# mcu.net
KiCad netlist of a schematic drawn in Altium Designer
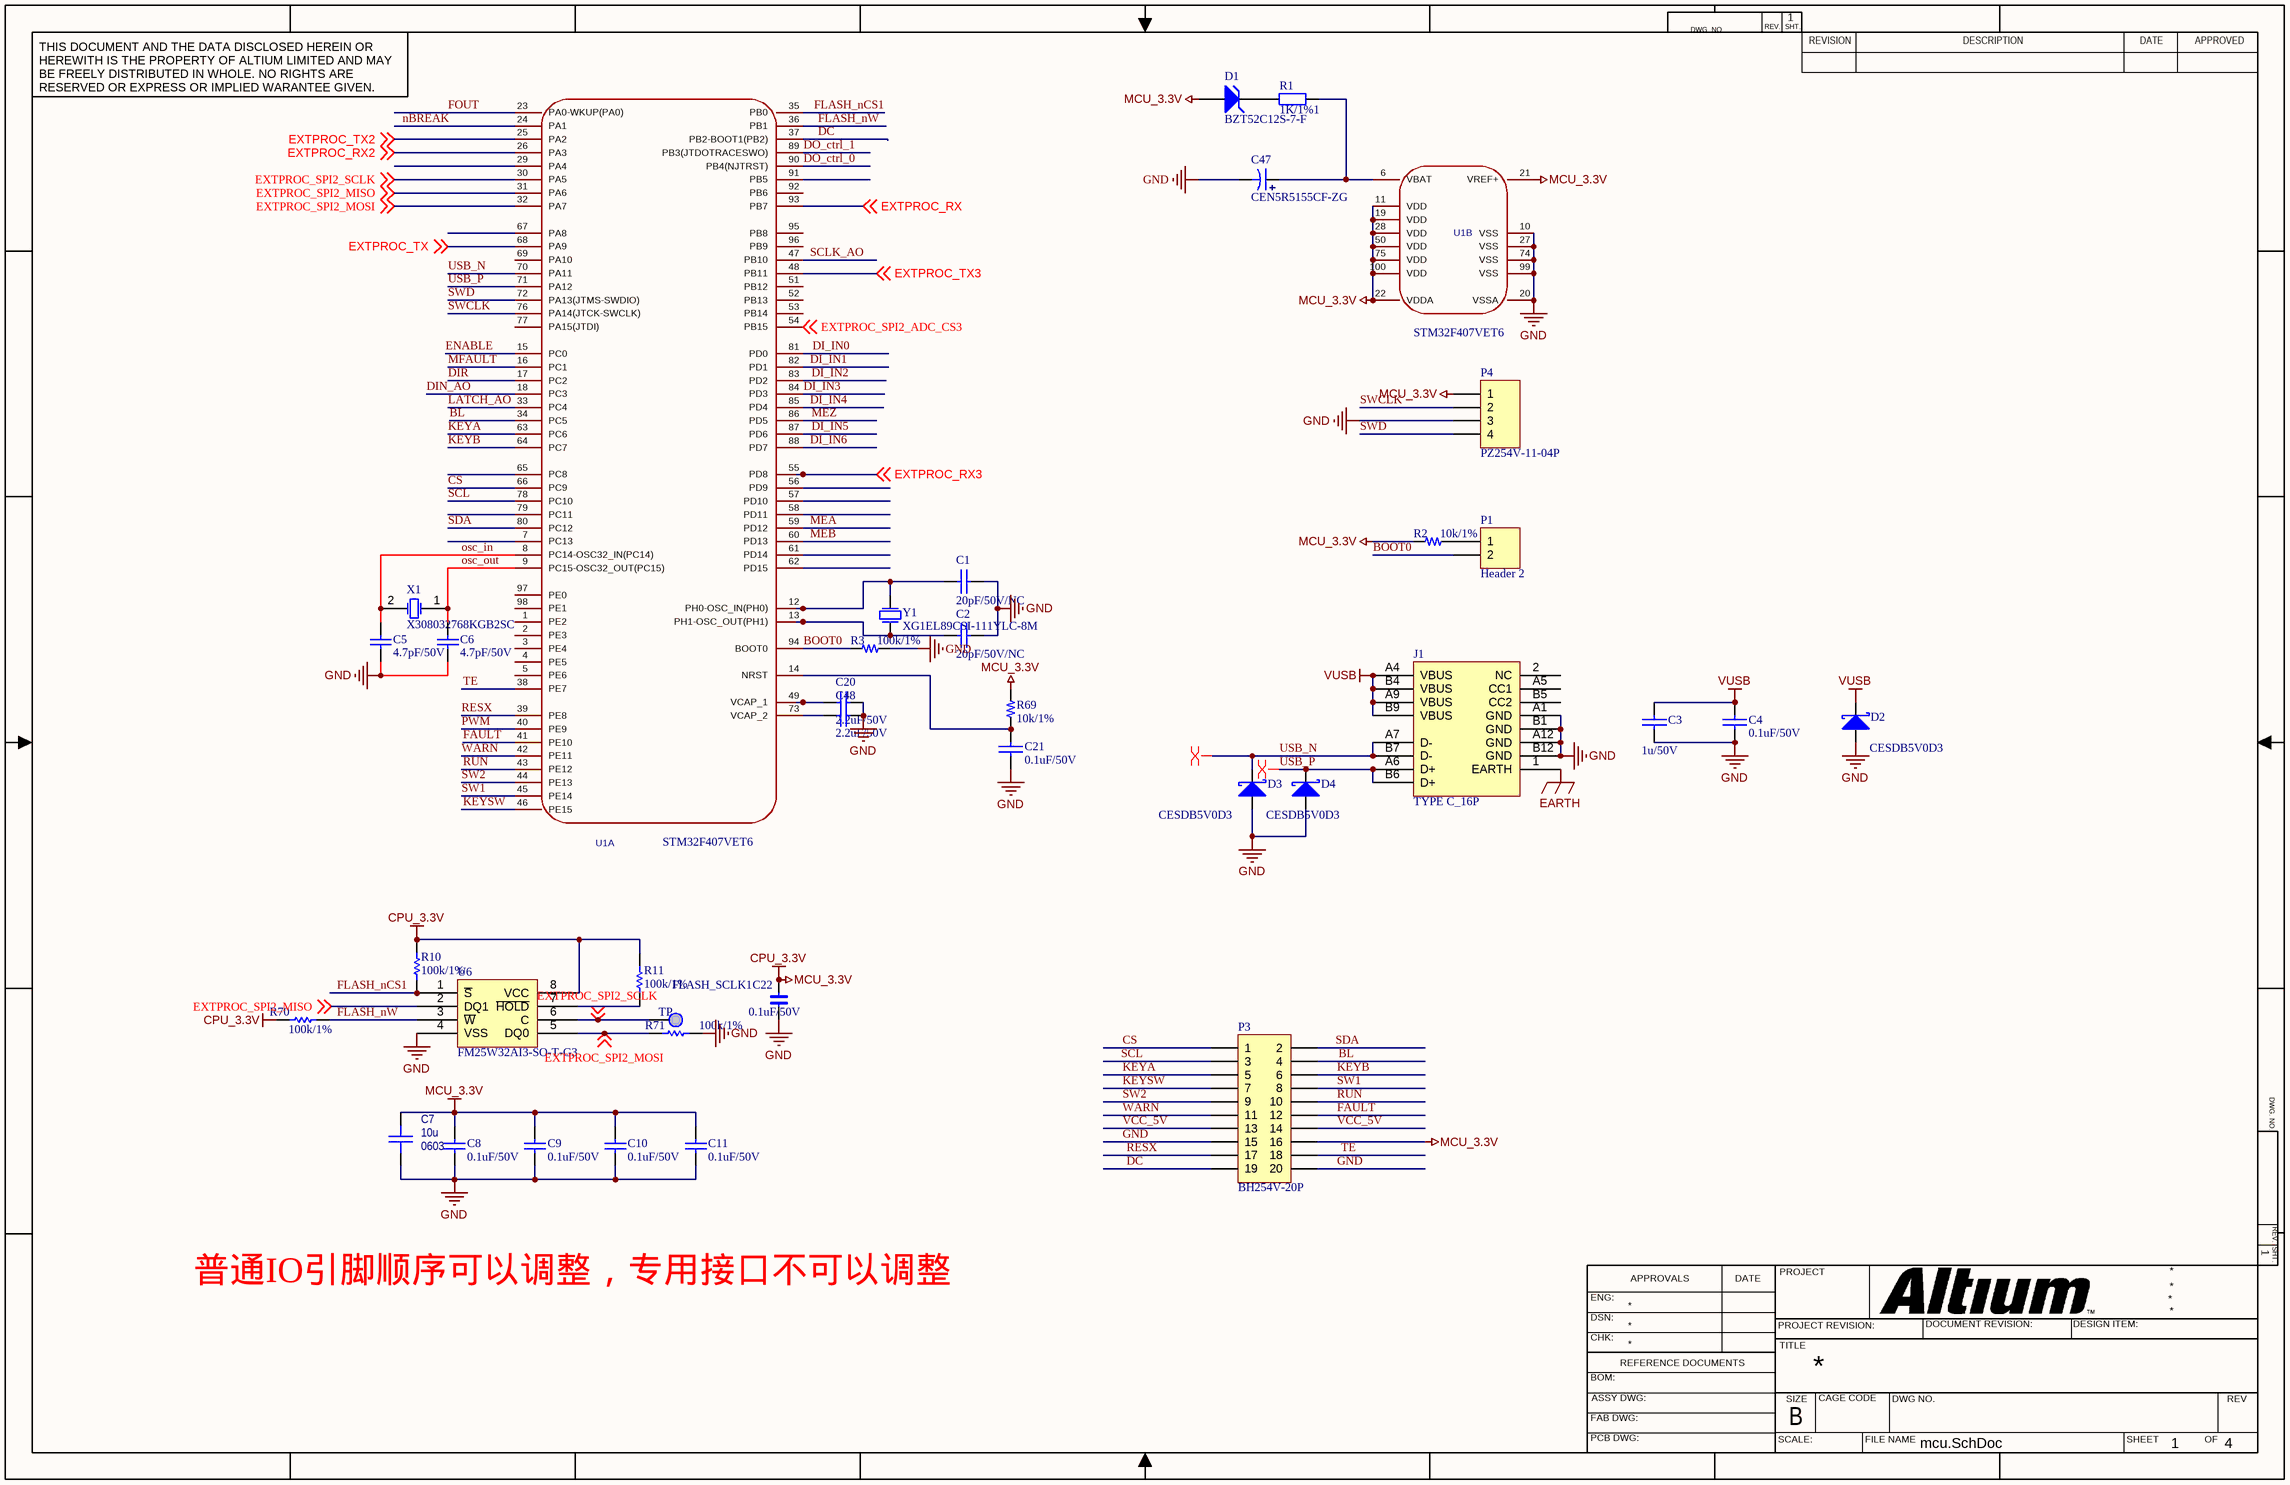
[diagram p0: mcu.SchDoc]

(export (version "E")
  (design (tool "Eeschema 10.0.6"))
  (components
    (comp (ref "C1")
      (value "20pF/50V/NC")
      (footprint "0603C")
      (fields (field (name "Comment") "20pF/25V/NC"))
      (libsource (lib "SM") (part "CAP"))
    )
    (comp (ref "C2")
      (value "20pF/50V/NC")
      (footprint "0603C")
      (fields (field (name "Comment") "20pF/25V/NC"))
      (libsource (lib "SM") (part "CAP"))
    )
    (comp (ref "C3") (value "1u/50V") (footprint "0603C") (libsource (lib "SM") (part "CAP")))
    (comp (ref "C4") (value "0.1uF/50V") (footprint "0603C") (libsource (lib "SM") (part "CAP")))
    (comp (ref "C5")
      (value "4.7pF/50V")
      (footprint "0603C")
      (description "Capacitor")
      (libsource (lib "Miscellaneous Devices") (part "Cap"))
    )
    (comp (ref "C6")
      (value "4.7pF/50V")
      (footprint "0603C")
      (description "Capacitor")
      (libsource (lib "Miscellaneous Devices") (part "Cap"))
    )
    (comp (ref "C7")
      (value "10u")
      (footprint "0603c")
      (description "Capacitor, MLCC")
      (fields (field (name "PACKAGE") "0603") (field (name "Comment") "10uF/16V"))
      (libsource (lib "Karl") (part "Capacitor_0603"))
    )
    (comp (ref "C8")
      (value "0.1uF/50V")
      (footprint "0603C")
      (description "Capacitor")
      (libsource (lib "Miscellaneous Devices") (part "Cap"))
    )
    (comp (ref "C9")
      (value "0.1uF/50V")
      (footprint "0603C")
      (description "Capacitor")
      (libsource (lib "Miscellaneous Devices") (part "Cap"))
    )
    (comp (ref "C10")
      (value "0.1uF/50V")
      (footprint "0603C")
      (description "Capacitor")
      (libsource (lib "Miscellaneous Devices") (part "Cap"))
    )
    (comp (ref "C11")
      (value "0.1uF/50V")
      (footprint "0603C")
      (description "Capacitor")
      (libsource (lib "Miscellaneous Devices") (part "Cap"))
    )
    (comp (ref "C20")
      (value "2.2uF/50V")
      (footprint "0603C")
      (description "Capacitor")
      (libsource (lib "Miscellaneous Devices") (part "Cap"))
    )
    (comp (ref "C21") (value "0.1uF/50V") (footprint "0603C") (libsource (lib "SM") (part "CAP")))
    (comp (ref "C22")
      (value "0.1uF/50V")
      (footprint "0603C")
      (description "C")
      (libsource (lib "Schlib_20110825") (part "C"))
    )
    (comp (ref "C47")
      (value "CEN5R5155CF-ZG")
      (footprint "DTU_V1.0:CAP-TH_BD21.0-P5.00-D0.8_CENXXX-CF")
      (description "电解电容")
      (libsource (lib "XiaoyI") (part "CAP2"))
    )
    (comp (ref "C48")
      (value "2.2uF/50V")
      (footprint "0603C")
      (description "Capacitor")
      (libsource (lib "Miscellaneous Devices") (part "Cap"))
    )
    (comp (ref "D1")
      (value "BZT52C12S-7-F")
      (footprint "DIOD-SOD323-2_V")
      (libsource (lib "Bogen") (part "BZT52C12S-7-F"))
    )
    (comp (ref "D2") (value "CESDB5V0D3") (footprint "SOD323") (libsource (lib "*") (part "DIODE S")))
    (comp (ref "D3") (value "CESDB5V0D3") (footprint "SOD323") (libsource (lib "*") (part "DIODE S")))
    (comp (ref "D4") (value "CESDB5V0D3") (footprint "SOD323") (libsource (lib "*") (part "DIODE S")))
    (comp (ref "FLASH_SCLK1") (value "TP") (footprint "tpd") (libsource (lib "Schlib1") (part "TP")))
    (comp (ref "J1")
      (value "TYPE C_16P")
      (footprint "TYPEC_16P")
      (libsource (lib "Schlib_20110825") (part "TYPE C_16P"))
    )
    (comp (ref "P1")
      (value "Header 2")
      (footprint "HDR1X2")
      (libsource (lib "Miscellaneous Connectors") (part "Header 2"))
    )
    (comp (ref "P3")
      (value "BH254V-20P")
      (footprint "IDC-TH_20P-L33.0-W13.8-H-M-R2-C10-P2.54-S2.54-TR")
      (description "Header, 10-Pin, Dual row")
      (libsource (lib "Miscellaneous Connectors") (part "Header 10X2"))
    )
    (comp (ref "P4")
      (value "PZ254V-11-04P")
      (footprint "HDR1X4")
      (libsource (lib "Miscellaneous Connectors") (part "Header 4"))
    )
    (comp (ref "R1") (value "1K/1%1") (footprint "0603R") (libsource (lib "MQlibrary") (part "Res0805M")))
    (comp (ref "R2") (value "10k/1%") (footprint "0603R") (libsource (lib "JRJ_1") (part "R")))
    (comp (ref "R3") (value "100k/1%") (footprint "0603R") (libsource (lib "JRJ_1") (part "R")))
    (comp (ref "R10")
      (value "100k/1%")
      (footprint "0603R")
      (description "Resistor")
      (libsource (lib "Miscellaneous Devices") (part "Res1"))
    )
    (comp (ref "R11")
      (value "100k/1%")
      (footprint "0603R")
      (description "Resistor")
      (libsource (lib "Miscellaneous Devices") (part "Res1"))
    )
    (comp (ref "R69") (value "10k/1%") (footprint "0603R") (libsource (lib "JRJ_1") (part "R")))
    (comp (ref "R70")
      (value "100k/1%")
      (footprint "0603R")
      (description "Resistor")
      (libsource (lib "Miscellaneous Devices") (part "Res1"))
    )
    (comp (ref "R71")
      (value "100k/1%")
      (footprint "0603R")
      (description "Resistor")
      (libsource (lib "Miscellaneous Devices") (part "Res1"))
    )
    (comp (ref "U1")
      (value "STM32F407VET6")
      (footprint "TQFP-100")
      (libsource (lib "altium-import") (part "root_0_STM32F407VET6_"))
    )
    (comp (ref "U6")
      (value "FM25W32AI3-SO-T-G3")
      (footprint "SOIC127P790X216-8N")
      (libsource (lib "Schlib1") (part "M25P16-VMN6TPBA"))
    )
    (comp (ref "X1")
      (value "X308032768KGB2SC")
      (footprint "A")
      (description "Crystal Oscillator")
      (libsource (lib "Miscellaneous Devices") (part "XTAL"))
    )
    (comp (ref "Y1")
      (value "XG1EL89CSI-111YLC-8M")
      (footprint "CRAY_5032")
      (libsource (lib "") (part "XTAL_1"))
    )
  )
  (nets
    (net (code "1") (name "/BL") (class "Default")
      (node (ref "P3") (pin "4") (pinfunction "4_4") (pintype "passive"))
      (node (ref "U1") (pin "34") (pinfunction "PC5_34") (pintype "passive"))
    )
    (net (code "2") (name "/BOOT0") (class "Default")
      (node (ref "P1") (pin "2") (pinfunction "2_2") (pintype "passive"))
      (node (ref "R3") (pin "1") (pintype "passive"))
      (node (ref "U1") (pin "94") (pinfunction "BOOT0_94") (pintype "passive"))
    )
    (net (code "3") (name "/CS") (class "Default")
      (node (ref "P3") (pin "1") (pinfunction "1_1") (pintype "passive"))
      (node (ref "U1") (pin "66") (pinfunction "PC9_66") (pintype "passive"))
    )
    (net (code "4") (name "/DC") (class "Default")
      (node (ref "P3") (pin "19") (pinfunction "19_19") (pintype "passive"))
      (node (ref "U1") (pin "37") (pinfunction "PB2-BOOT1(PB2)_37") (pintype "passive"))
    )
    (net (code "5") (name "/DIN_AO") (class "Default")
      (node (ref "U1") (pin "18") (pinfunction "PC3_18") (pintype "passive"))
    )
    (net (code "6") (name "/DIR") (class "Default")
      (node (ref "U1") (pin "17") (pinfunction "PC2_17") (pintype "passive"))
    )
    (net (code "7") (name "/DI_IN0") (class "Default")
      (node (ref "U1") (pin "81") (pinfunction "PD0_81") (pintype "passive"))
    )
    (net (code "8") (name "/DI_IN1") (class "Default")
      (node (ref "U1") (pin "82") (pinfunction "PD1_82") (pintype "passive"))
    )
    (net (code "9") (name "/DI_IN2") (class "Default")
      (node (ref "U1") (pin "83") (pinfunction "PD2_83") (pintype "passive"))
    )
    (net (code "10") (name "/DI_IN3") (class "Default")
      (node (ref "U1") (pin "84") (pinfunction "PD3_84") (pintype "passive"))
    )
    (net (code "11") (name "/DI_IN4") (class "Default")
      (node (ref "U1") (pin "85") (pinfunction "PD4_85") (pintype "passive"))
    )
    (net (code "12") (name "/DI_IN5") (class "Default")
      (node (ref "U1") (pin "87") (pinfunction "PD6_87") (pintype "passive"))
    )
    (net (code "13") (name "/DI_IN6") (class "Default")
      (node (ref "U1") (pin "88") (pinfunction "PD7_88") (pintype "passive"))
    )
    (net (code "14") (name "/DO_ctrl_0") (class "Default")
      (node (ref "U1") (pin "90") (pinfunction "PB4(NJTRST)_90") (pintype "passive"))
    )
    (net (code "15") (name "/DO_ctrl_1") (class "Default")
      (node (ref "U1") (pin "89") (pinfunction "PB3(JTDOTRACESWO)_89") (pintype "passive"))
    )
    (net (code "16") (name "/ENABLE") (class "Default")
      (node (ref "U1") (pin "15") (pinfunction "PC0_15") (pintype "passive"))
    )
    (net (code "17") (name "/FAULT") (class "Default")
      (node (ref "P3") (pin "12") (pinfunction "12_12") (pintype "passive"))
      (node (ref "U1") (pin "41") (pinfunction "PE10_41") (pintype "passive"))
    )
    (net (code "18") (name "/FLASH_nCS1") (class "Default")
      (node (ref "R10") (pin "2") (pinfunction "2_2") (pintype "passive"))
      (node (ref "U1") (pin "35") (pinfunction "PB0_35") (pintype "passive"))
      (node (ref "U6") (pin "1") (pinfunction "~{S}_1") (pintype "passive"))
    )
    (net (code "19") (name "/FLASH_nW") (class "Default")
      (node (ref "R70") (pin "2") (pinfunction "2_2") (pintype "passive"))
      (node (ref "U1") (pin "36") (pinfunction "PB1_36") (pintype "passive"))
      (node (ref "U6") (pin "3") (pinfunction "~{W}_3") (pintype "passive"))
    )
    (net (code "20") (name "/FOUT") (class "Default")
      (node (ref "U1") (pin "23") (pinfunction "PA0-WKUP(PA0)_23") (pintype "passive"))
    )
    (net (code "21") (name "/KEYA") (class "Default")
      (node (ref "P3") (pin "5") (pinfunction "5_5") (pintype "passive"))
      (node (ref "U1") (pin "63") (pinfunction "PC6_63") (pintype "passive"))
    )
    (net (code "22") (name "/KEYB") (class "Default")
      (node (ref "P3") (pin "6") (pinfunction "6_6") (pintype "passive"))
      (node (ref "U1") (pin "64") (pinfunction "PC7_64") (pintype "passive"))
    )
    (net (code "23") (name "/KEYSW") (class "Default")
      (node (ref "P3") (pin "7") (pinfunction "7_7") (pintype "passive"))
      (node (ref "U1") (pin "46") (pinfunction "PE15_46") (pintype "passive"))
    )
    (net (code "24") (name "/LATCH_AO") (class "Default")
      (node (ref "U1") (pin "33") (pinfunction "PC4_33") (pintype "passive"))
    )
    (net (code "25") (name "/MEA") (class "Default")
      (node (ref "U1") (pin "59") (pinfunction "PD12_59") (pintype "passive"))
    )
    (net (code "26") (name "/MEB") (class "Default")
      (node (ref "U1") (pin "60") (pinfunction "PD13_60") (pintype "passive"))
    )
    (net (code "27") (name "/MEZ") (class "Default")
      (node (ref "U1") (pin "86") (pinfunction "PD5_86") (pintype "passive"))
    )
    (net (code "28") (name "/MFAULT") (class "Default")
      (node (ref "U1") (pin "16") (pinfunction "PC1_16") (pintype "passive"))
    )
    (net (code "29") (name "/PWM") (class "Default")
      (node (ref "U1") (pin "40") (pinfunction "PE9_40") (pintype "passive"))
    )
    (net (code "30") (name "/RESX") (class "Default")
      (node (ref "P3") (pin "17") (pinfunction "17_17") (pintype "passive"))
      (node (ref "U1") (pin "39") (pinfunction "PE8_39") (pintype "passive"))
    )
    (net (code "31") (name "/RUN") (class "Default")
      (node (ref "P3") (pin "10") (pinfunction "10_10") (pintype "passive"))
      (node (ref "U1") (pin "43") (pinfunction "PE12_43") (pintype "passive"))
    )
    (net (code "32") (name "/SCL") (class "Default")
      (node (ref "P3") (pin "3") (pinfunction "3_3") (pintype "passive"))
      (node (ref "U1") (pin "78") (pinfunction "PC10_78") (pintype "passive"))
    )
    (net (code "33") (name "/SCLK_AO") (class "Default")
      (node (ref "U1") (pin "47") (pinfunction "PB10_47") (pintype "passive"))
    )
    (net (code "34") (name "/SDA") (class "Default")
      (node (ref "P3") (pin "2") (pinfunction "2_2") (pintype "passive"))
      (node (ref "U1") (pin "80") (pinfunction "PC12_80") (pintype "passive"))
    )
    (net (code "35") (name "/SW1") (class "Default")
      (node (ref "P3") (pin "8") (pinfunction "8_8") (pintype "passive"))
      (node (ref "U1") (pin "45") (pinfunction "PE14_45") (pintype "passive"))
    )
    (net (code "36") (name "/SW2") (class "Default")
      (node (ref "P3") (pin "9") (pinfunction "9_9") (pintype "passive"))
      (node (ref "U1") (pin "44") (pinfunction "PE13_44") (pintype "passive"))
    )
    (net (code "37") (name "/SWCLK") (class "Default")
      (node (ref "P4") (pin "2") (pinfunction "2_2") (pintype "passive"))
      (node (ref "U1") (pin "76") (pinfunction "PA14(JTCK-SWCLK)_76") (pintype "passive"))
    )
    (net (code "38") (name "/SWD") (class "Default")
      (node (ref "P4") (pin "4") (pinfunction "4_4") (pintype "passive"))
      (node (ref "U1") (pin "72") (pinfunction "PA13(JTMS-SWDIO)_72") (pintype "passive"))
    )
    (net (code "39") (name "/TE") (class "Default")
      (node (ref "P3") (pin "18") (pinfunction "18_18") (pintype "passive"))
      (node (ref "U1") (pin "38") (pinfunction "PE7_38") (pintype "passive"))
    )
    (net (code "40") (name "/USB_N") (class "Default")
      (node (ref "D3") (pin "2") (pinfunction "K_2") (pintype "passive"))
      (node (ref "J1") (pin "A7") (pinfunction "D-_A7") (pintype "passive"))
      (node (ref "J1") (pin "B7") (pinfunction "D-_B7") (pintype "passive"))
      (node (ref "U1") (pin "70") (pinfunction "PA11_70") (pintype "passive"))
    )
    (net (code "41") (name "/USB_P") (class "Default")
      (node (ref "D4") (pin "2") (pinfunction "K_2") (pintype "passive"))
      (node (ref "J1") (pin "A6") (pinfunction "D+_A6") (pintype "passive"))
      (node (ref "J1") (pin "B6") (pinfunction "D+_B6") (pintype "passive"))
      (node (ref "U1") (pin "71") (pinfunction "PA12_71") (pintype "passive"))
    )
    (net (code "42") (name "/VCC_5V") (class "Default")
      (node (ref "P3") (pin "13") (pinfunction "13_13") (pintype "passive"))
      (node (ref "P3") (pin "14") (pinfunction "14_14") (pintype "passive"))
    )
    (net (code "43") (name "/WARN") (class "Default")
      (node (ref "P3") (pin "11") (pinfunction "11_11") (pintype "passive"))
      (node (ref "U1") (pin "42") (pinfunction "PE11_42") (pintype "passive"))
    )
    (net (code "44") (name "/nBREAK") (class "Default")
      (node (ref "U1") (pin "24") (pinfunction "PA1_24") (pintype "passive"))
    )
    (net (code "45") (name "/osc_in") (class "Default")
      (node (ref "C5") (pin "1") (pinfunction "1_1") (pintype "passive"))
      (node (ref "U1") (pin "8") (pinfunction "PC14-OSC32_IN(PC14)_8") (pintype "passive"))
      (node (ref "X1") (pin "2") (pinfunction "OSC2_2") (pintype "passive"))
    )
    (net (code "46") (name "/osc_out") (class "Default")
      (node (ref "C6") (pin "1") (pinfunction "1_1") (pintype "passive"))
      (node (ref "U1") (pin "9") (pinfunction "PC15-OSC32_OUT(PC15)_9") (pintype "passive"))
      (node (ref "X1") (pin "1") (pinfunction "OSC1_1") (pintype "passive"))
    )
    (net (code "47") (name "CPU_3.3V") (class "Default")
      (node (ref "C10") (pin "2") (pinfunction "2_2") (pintype "passive"))
      (node (ref "C11") (pin "2") (pinfunction "2_2") (pintype "passive"))
      (node (ref "C22") (pin "2") (pintype "passive"))
      (node (ref "C7") (pin "1") (pinfunction "1_1") (pintype "passive"))
      (node (ref "C8") (pin "2") (pinfunction "2_2") (pintype "passive"))
      (node (ref "C9") (pin "2") (pinfunction "2_2") (pintype "passive"))
      (node (ref "D1") (pin "1") (pinfunction "A_1") (pintype "passive"))
      (node (ref "P3") (pin "16") (pinfunction "16_16") (pintype "passive"))
      (node (ref "P4") (pin "1") (pinfunction "1_1") (pintype "passive"))
      (node (ref "R10") (pin "1") (pinfunction "1_1") (pintype "passive"))
      (node (ref "R11") (pin "1") (pinfunction "1_1") (pintype "passive"))
      (node (ref "R2") (pin "1") (pintype "passive"))
      (node (ref "R69") (pin "1") (pintype "passive"))
      (node (ref "R70") (pin "1") (pinfunction "1_1") (pintype "passive"))
      (node (ref "U1") (pin "100") (pinfunction "VDD_100") (pintype "passive"))
      (node (ref "U1") (pin "11") (pinfunction "VDD_11") (pintype "passive"))
      (node (ref "U1") (pin "19") (pinfunction "VDD_19") (pintype "passive"))
      (node (ref "U1") (pin "21") (pinfunction "VREF+_21") (pintype "passive"))
      (node (ref "U1") (pin "22") (pinfunction "VDDA_22") (pintype "passive"))
      (node (ref "U1") (pin "28") (pinfunction "VDD_28") (pintype "passive"))
      (node (ref "U1") (pin "50") (pinfunction "VDD_50") (pintype "passive"))
      (node (ref "U1") (pin "75") (pinfunction "VDD_75") (pintype "passive"))
      (node (ref "U6") (pin "8") (pinfunction "VCC_8") (pintype "passive"))
    )
    (net (code "48") (name "EARTH") (class "Default")
      (node (ref "J1") (pin "1") (pinfunction "EARTH_1") (pintype "passive"))
    )
    (net (code "49") (name "EXTPROC_RX") (class "Default")
      (node (ref "U1") (pin "93") (pinfunction "PB7_93") (pintype "passive"))
    )
    (net (code "50") (name "EXTPROC_RX2") (class "Default")
      (node (ref "U1") (pin "26") (pinfunction "PA3_26") (pintype "passive"))
    )
    (net (code "51") (name "EXTPROC_RX3") (class "Default")
      (node (ref "U1") (pin "55") (pinfunction "PD8_55") (pintype "passive"))
    )
    (net (code "52") (name "EXTPROC_SPI2_ADC_CS3") (class "Default")
      (node (ref "U1") (pin "54") (pinfunction "PB15_54") (pintype "passive"))
    )
    (net (code "53") (name "EXTPROC_SPI2_MISO") (class "Default")
      (node (ref "U1") (pin "31") (pinfunction "PA6_31") (pintype "passive"))
      (node (ref "U6") (pin "2") (pinfunction "DQ1_2") (pintype "passive"))
    )
    (net (code "54") (name "EXTPROC_SPI2_MOSI") (class "Default")
      (node (ref "R71") (pin "1") (pinfunction "1_1") (pintype "passive"))
      (node (ref "U1") (pin "32") (pinfunction "PA7_32") (pintype "passive"))
      (node (ref "U6") (pin "5") (pinfunction "DQ0_5") (pintype "passive"))
    )
    (net (code "55") (name "EXTPROC_SPI2_SCLK") (class "Default")
      (node (ref "FLASH_SCLK1") (pin "1") (pinfunction "1_1") (pintype "passive"))
      (node (ref "U1") (pin "30") (pinfunction "PA5_30") (pintype "passive"))
      (node (ref "U6") (pin "6") (pinfunction "C_6") (pintype "passive"))
    )
    (net (code "56") (name "EXTPROC_TX") (class "Default")
      (node (ref "U1") (pin "68") (pinfunction "PA9_68") (pintype "passive"))
    )
    (net (code "57") (name "EXTPROC_TX2") (class "Default")
      (node (ref "U1") (pin "25") (pinfunction "PA2_25") (pintype "passive"))
    )
    (net (code "58") (name "EXTPROC_TX3") (class "Default")
      (node (ref "U1") (pin "48") (pinfunction "PB11_48") (pintype "passive"))
    )
    (net (code "59") (name "GND") (class "Default")
      (node (ref "C1") (pin "2") (pinfunction "2_2") (pintype "passive"))
      (node (ref "C10") (pin "1") (pinfunction "1_1") (pintype "passive"))
      (node (ref "C11") (pin "1") (pinfunction "1_1") (pintype "passive"))
      (node (ref "C2") (pin "2") (pinfunction "2_2") (pintype "passive"))
      (node (ref "C20") (pin "1") (pinfunction "1_1") (pintype "passive"))
      (node (ref "C21") (pin "1") (pinfunction "1_1") (pintype "passive"))
      (node (ref "C22") (pin "1") (pintype "passive"))
      (node (ref "C3") (pin "1") (pinfunction "1_1") (pintype "passive"))
      (node (ref "C4") (pin "1") (pinfunction "1_1") (pintype "passive"))
      (node (ref "C47") (pin "2") (pinfunction "2_2") (pintype "passive"))
      (node (ref "C48") (pin "1") (pinfunction "1_1") (pintype "passive"))
      (node (ref "C5") (pin "2") (pinfunction "2_2") (pintype "passive"))
      (node (ref "C6") (pin "2") (pinfunction "2_2") (pintype "passive"))
      (node (ref "C7") (pin "2") (pinfunction "2_2") (pintype "passive"))
      (node (ref "C8") (pin "1") (pinfunction "1_1") (pintype "passive"))
      (node (ref "C9") (pin "1") (pinfunction "1_1") (pintype "passive"))
      (node (ref "D2") (pin "1") (pinfunction "A_1") (pintype "passive"))
      (node (ref "D3") (pin "1") (pinfunction "A_1") (pintype "passive"))
      (node (ref "D4") (pin "1") (pinfunction "A_1") (pintype "passive"))
      (node (ref "J1") (pin "A1") (pinfunction "GND_A1") (pintype "passive"))
      (node (ref "J1") (pin "A12") (pinfunction "GND_A12") (pintype "passive"))
      (node (ref "J1") (pin "B1") (pinfunction "GND_B1") (pintype "passive"))
      (node (ref "J1") (pin "B12") (pinfunction "GND_B12") (pintype "passive"))
      (node (ref "P3") (pin "15") (pinfunction "15_15") (pintype "passive"))
      (node (ref "P3") (pin "20") (pinfunction "20_20") (pintype "passive"))
      (node (ref "P4") (pin "3") (pinfunction "3_3") (pintype "passive"))
      (node (ref "R3") (pin "2") (pintype "passive"))
      (node (ref "R71") (pin "2") (pinfunction "2_2") (pintype "passive"))
      (node (ref "U1") (pin "10") (pinfunction "VSS_10") (pintype "passive"))
      (node (ref "U1") (pin "20") (pinfunction "VSSA_20") (pintype "passive"))
      (node (ref "U1") (pin "27") (pinfunction "VSS_27") (pintype "passive"))
      (node (ref "U1") (pin "74") (pinfunction "VSS_74") (pintype "passive"))
      (node (ref "U1") (pin "99") (pinfunction "VSS_99") (pintype "passive"))
      (node (ref "U6") (pin "4") (pinfunction "VSS_4") (pintype "passive"))
    )
    (net (code "60") (name "Net-(D1-K)") (class "Default")
      (node (ref "D1") (pin "2") (pinfunction "K_2") (pintype "passive"))
      (node (ref "R1") (pin "1") (pinfunction "1_1") (pintype "passive"))
    )
    (net (code "61") (name "Net-(P1-Pad1)") (class "Default")
      (node (ref "P1") (pin "1") (pinfunction "1_1") (pintype "passive"))
      (node (ref "R2") (pin "2") (pintype "passive"))
    )
    (net (code "62") (name "Net-(U1A-NRST)") (class "Default")
      (node (ref "C21") (pin "2") (pinfunction "2_2") (pintype "passive"))
      (node (ref "R69") (pin "2") (pintype "passive"))
      (node (ref "U1") (pin "14") (pinfunction "NRST_14") (pintype "passive"))
    )
    (net (code "63") (name "Net-(U1A-PH0-OSC_IN(PH0))") (class "Default")
      (node (ref "C1") (pin "1") (pinfunction "1_1") (pintype "passive"))
      (node (ref "U1") (pin "12") (pinfunction "PH0-OSC_IN(PH0)_12") (pintype "passive"))
      (node (ref "Y1") (pin "2") (pinfunction "P2_2") (pintype "passive"))
    )
    (net (code "64") (name "Net-(U1A-PH1-OSC_OUT(PH1))") (class "Default")
      (node (ref "C2") (pin "1") (pinfunction "1_1") (pintype "passive"))
      (node (ref "U1") (pin "13") (pinfunction "PH1-OSC_OUT(PH1)_13") (pintype "passive"))
      (node (ref "Y1") (pin "1") (pinfunction "P1_1") (pintype "passive"))
    )
    (net (code "65") (name "Net-(U1A-VCAP_1)") (class "Default")
      (node (ref "C20") (pin "2") (pinfunction "2_2") (pintype "passive"))
      (node (ref "U1") (pin "49") (pinfunction "VCAP_1_49") (pintype "passive"))
    )
    (net (code "66") (name "Net-(U1A-VCAP_2)") (class "Default")
      (node (ref "C48") (pin "2") (pinfunction "2_2") (pintype "passive"))
      (node (ref "U1") (pin "73") (pinfunction "VCAP_2_73") (pintype "passive"))
    )
    (net (code "67") (name "Net-(U1B-VBAT)") (class "Default")
      (node (ref "C47") (pin "1") (pinfunction "1_1") (pintype "passive"))
      (node (ref "R1") (pin "2") (pinfunction "2_2") (pintype "passive"))
      (node (ref "U1") (pin "6") (pinfunction "VBAT_6") (pintype "passive"))
    )
    (net (code "68") (name "Net-(U6-~{HOLD})") (class "Default")
      (node (ref "R11") (pin "2") (pinfunction "2_2") (pintype "passive"))
      (node (ref "U6") (pin "7") (pinfunction "~{HOLD}_7") (pintype "passive"))
    )
    (net (code "69") (name "VUSB") (class "Default")
      (node (ref "C3") (pin "2") (pinfunction "2_2") (pintype "passive"))
      (node (ref "C4") (pin "2") (pinfunction "2_2") (pintype "passive"))
      (node (ref "D2") (pin "2") (pinfunction "K_2") (pintype "passive"))
      (node (ref "J1") (pin "A4") (pinfunction "VBUS_A4") (pintype "passive"))
      (node (ref "J1") (pin "A9") (pinfunction "VBUS_A9") (pintype "passive"))
      (node (ref "J1") (pin "B4") (pinfunction "VBUS_B4") (pintype "passive"))
      (node (ref "J1") (pin "B9") (pinfunction "VBUS_B9") (pintype "passive"))
    )
    (net (code "70") (name "unconnected-(J1-CC1-PadA5)") (class "Default")
      (node (ref "J1") (pin "A5") (pinfunction "CC1_A5") (pintype "passive"))
    )
    (net (code "71") (name "unconnected-(J1-CC2-PadB5)") (class "Default")
      (node (ref "J1") (pin "B5") (pinfunction "CC2_B5") (pintype "passive"))
    )
    (net (code "72") (name "unconnected-(J1-NC-Pad2)") (class "Default")
      (node (ref "J1") (pin "2") (pinfunction "NC_2") (pintype "passive"))
    )
    (net (code "73") (name "unconnected-(U1A-PA4-Pad29)") (class "Default")
      (node (ref "U1") (pin "29") (pinfunction "PA4_29") (pintype "passive"))
    )
    (net (code "74") (name "unconnected-(U1A-PA8-Pad67)") (class "Default")
      (node (ref "U1") (pin "67") (pinfunction "PA8_67") (pintype "passive"))
    )
    (net (code "75") (name "unconnected-(U1A-PA10-Pad69)") (class "Default")
      (node (ref "U1") (pin "69") (pinfunction "PA10_69") (pintype "passive"))
    )
    (net (code "76") (name "unconnected-(U1A-PA15(JTDI)-Pad77)") (class "Default")
      (node (ref "U1") (pin "77") (pinfunction "PA15(JTDI)_77") (pintype "passive"))
    )
    (net (code "77") (name "unconnected-(U1A-PB5-Pad91)") (class "Default")
      (node (ref "U1") (pin "91") (pinfunction "PB5_91") (pintype "passive"))
    )
    (net (code "78") (name "unconnected-(U1A-PB6-Pad92)") (class "Default")
      (node (ref "U1") (pin "92") (pinfunction "PB6_92") (pintype "passive"))
    )
    (net (code "79") (name "unconnected-(U1A-PB8-Pad95)") (class "Default")
      (node (ref "U1") (pin "95") (pinfunction "PB8_95") (pintype "passive"))
    )
    (net (code "80") (name "unconnected-(U1A-PB9-Pad96)") (class "Default")
      (node (ref "U1") (pin "96") (pinfunction "PB9_96") (pintype "passive"))
    )
    (net (code "81") (name "unconnected-(U1A-PB12-Pad51)") (class "Default")
      (node (ref "U1") (pin "51") (pinfunction "PB12_51") (pintype "passive"))
    )
    (net (code "82") (name "unconnected-(U1A-PB13-Pad52)") (class "Default")
      (node (ref "U1") (pin "52") (pinfunction "PB13_52") (pintype "passive"))
    )
    (net (code "83") (name "unconnected-(U1A-PB14-Pad53)") (class "Default")
      (node (ref "U1") (pin "53") (pinfunction "PB14_53") (pintype "passive"))
    )
    (net (code "84") (name "unconnected-(U1A-PC8-Pad65)") (class "Default")
      (node (ref "U1") (pin "65") (pinfunction "PC8_65") (pintype "passive"))
    )
    (net (code "85") (name "unconnected-(U1A-PC11-Pad79)") (class "Default")
      (node (ref "U1") (pin "79") (pinfunction "PC11_79") (pintype "passive"))
    )
    (net (code "86") (name "unconnected-(U1A-PC13-Pad7)") (class "Default")
      (node (ref "U1") (pin "7") (pinfunction "PC13_7") (pintype "passive"))
    )
    (net (code "87") (name "unconnected-(U1A-PD9-Pad56)") (class "Default")
      (node (ref "U1") (pin "56") (pinfunction "PD9_56") (pintype "passive"))
    )
    (net (code "88") (name "unconnected-(U1A-PD10-Pad57)") (class "Default")
      (node (ref "U1") (pin "57") (pinfunction "PD10_57") (pintype "passive"))
    )
    (net (code "89") (name "unconnected-(U1A-PD11-Pad58)") (class "Default")
      (node (ref "U1") (pin "58") (pinfunction "PD11_58") (pintype "passive"))
    )
    (net (code "90") (name "unconnected-(U1A-PD14-Pad61)") (class "Default")
      (node (ref "U1") (pin "61") (pinfunction "PD14_61") (pintype "passive"))
    )
    (net (code "91") (name "unconnected-(U1A-PD15-Pad62)") (class "Default")
      (node (ref "U1") (pin "62") (pinfunction "PD15_62") (pintype "passive"))
    )
    (net (code "92") (name "unconnected-(U1A-PE0-Pad97)") (class "Default")
      (node (ref "U1") (pin "97") (pinfunction "PE0_97") (pintype "passive"))
    )
    (net (code "93") (name "unconnected-(U1A-PE1-Pad98)") (class "Default")
      (node (ref "U1") (pin "98") (pinfunction "PE1_98") (pintype "passive"))
    )
    (net (code "94") (name "unconnected-(U1A-PE2-Pad1)") (class "Default")
      (node (ref "U1") (pin "1") (pinfunction "PE2_1") (pintype "passive"))
    )
    (net (code "95") (name "unconnected-(U1A-PE3-Pad2)") (class "Default")
      (node (ref "U1") (pin "2") (pinfunction "PE3_2") (pintype "passive"))
    )
    (net (code "96") (name "unconnected-(U1A-PE4-Pad3)") (class "Default")
      (node (ref "U1") (pin "3") (pinfunction "PE4_3") (pintype "passive"))
    )
    (net (code "97") (name "unconnected-(U1A-PE5-Pad4)") (class "Default")
      (node (ref "U1") (pin "4") (pinfunction "PE5_4") (pintype "passive"))
    )
    (net (code "98") (name "unconnected-(U1A-PE6-Pad5)") (class "Default")
      (node (ref "U1") (pin "5") (pinfunction "PE6_5") (pintype "passive"))
    )
  )
)
